# zx81_kbd.net
KiCad netlist of a schematic drawn in EAGLE
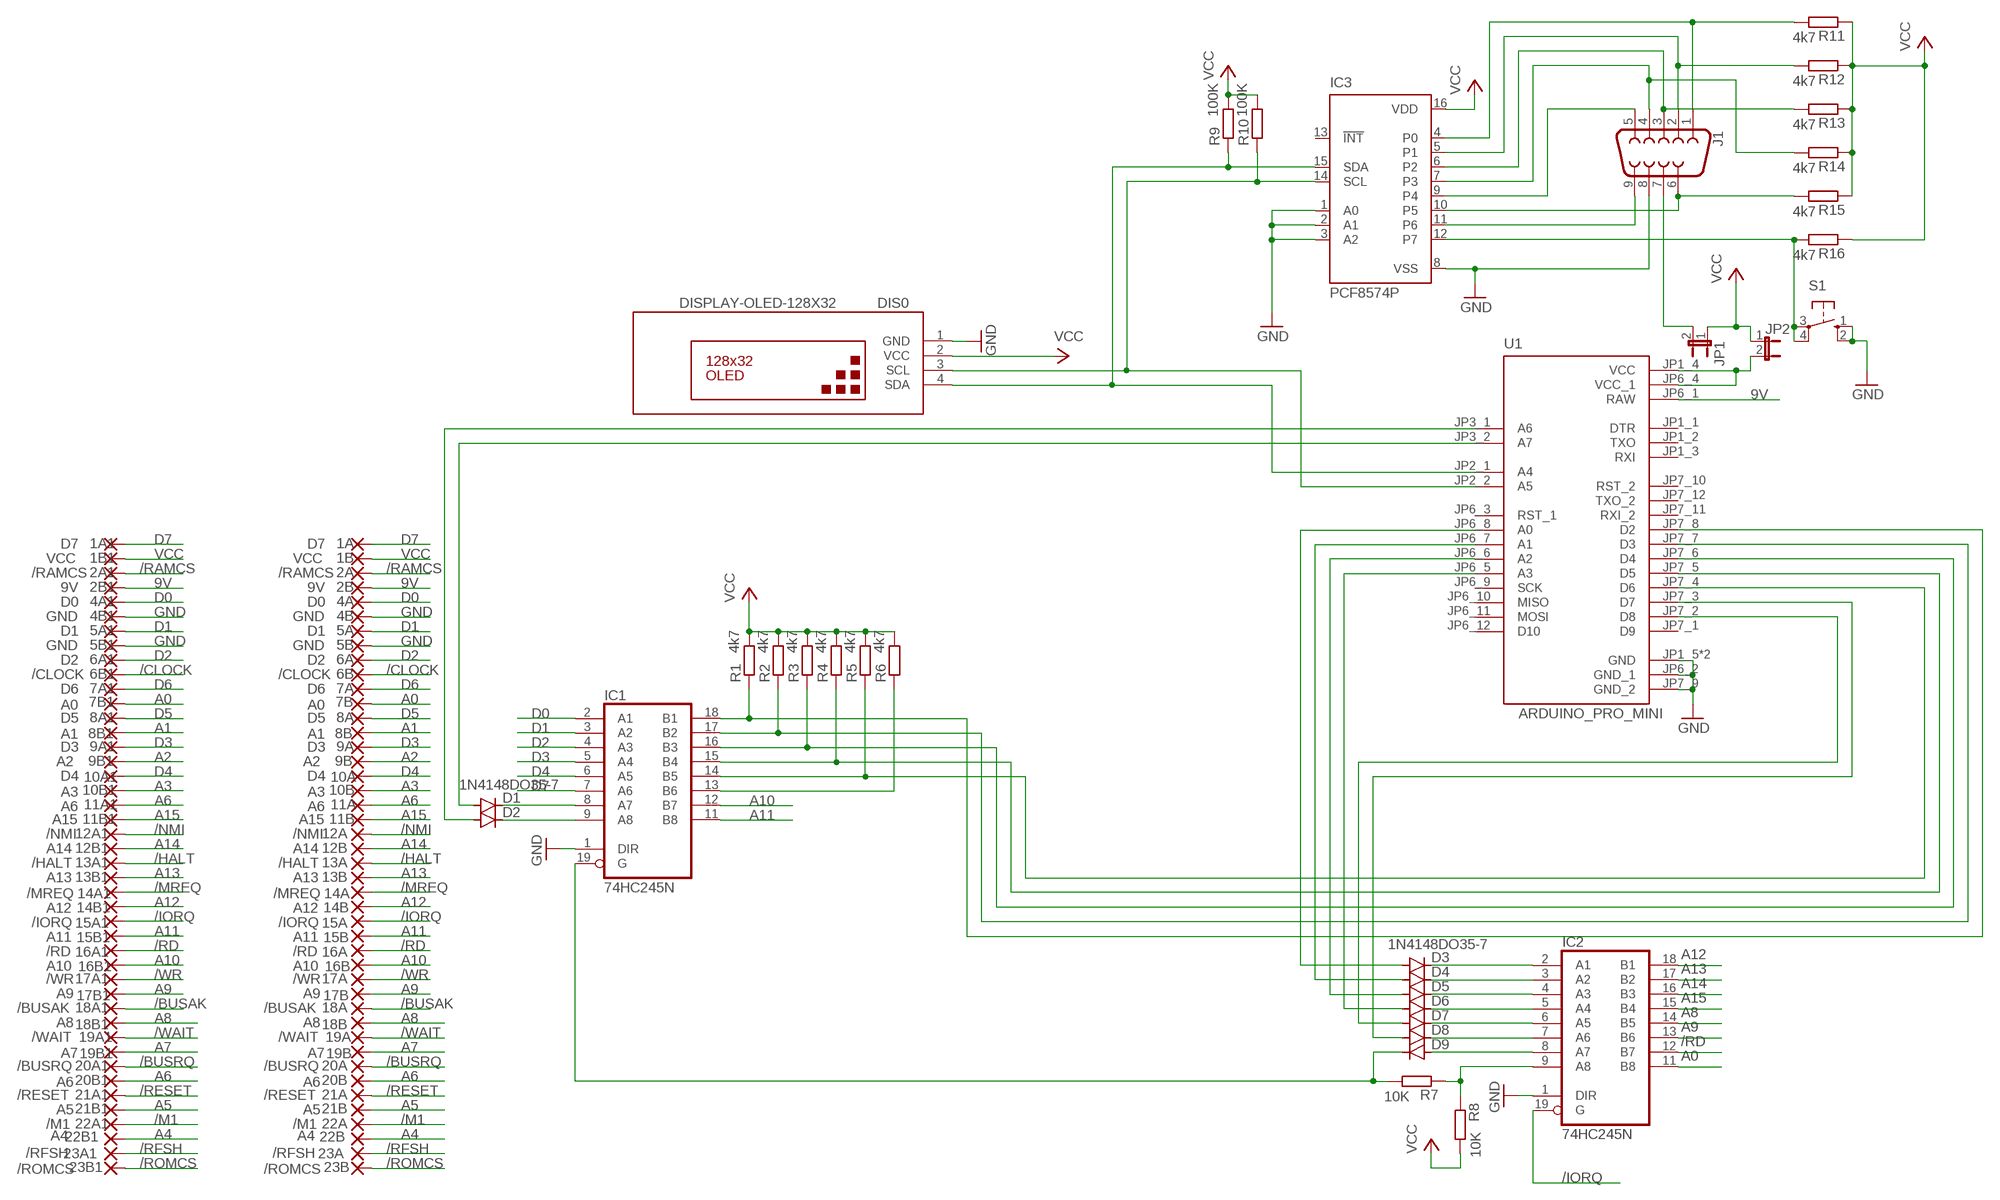
[diagram p0: schematic, sheet 1]

(export (version "E")
  (design (tool "Eeschema 10.0.6"))
  (components
    (comp (ref "1A")
      (value "D7")
      (footprint "eagle-import:EDGEPIN")
      (libsource (lib "eagle-import") (part "SMD2EDGEPIN"))
    )
    (comp (ref "1A1")
      (value "D7")
      (footprint "eagle-import:EDGEPIN")
      (libsource (lib "eagle-import") (part "SMD2EDGEPIN"))
    )
    (comp (ref "1B")
      (value "VCC")
      (footprint "eagle-import:EDGEPIN")
      (libsource (lib "eagle-import") (part "SMD2EDGEPIN"))
    )
    (comp (ref "1B1")
      (value "VCC")
      (footprint "eagle-import:EDGEPIN")
      (libsource (lib "eagle-import") (part "SMD2EDGEPIN"))
    )
    (comp (ref "2A")
      (value "/RAMCS")
      (footprint "eagle-import:EDGEPIN")
      (libsource (lib "eagle-import") (part "SMD2EDGEPIN"))
    )
    (comp (ref "2A1")
      (value "/RAMCS")
      (footprint "eagle-import:EDGEPIN")
      (libsource (lib "eagle-import") (part "SMD2EDGEPIN"))
    )
    (comp (ref "2B")
      (value "9V")
      (footprint "eagle-import:EDGEPIN")
      (libsource (lib "eagle-import") (part "SMD2EDGEPIN"))
    )
    (comp (ref "2B1")
      (value "9V")
      (footprint "eagle-import:EDGEPIN")
      (libsource (lib "eagle-import") (part "SMD2EDGEPIN"))
    )
    (comp (ref "4A")
      (value "D0")
      (footprint "eagle-import:EDGEPIN")
      (libsource (lib "eagle-import") (part "SMD2EDGEPIN"))
    )
    (comp (ref "4A1")
      (value "D0")
      (footprint "eagle-import:EDGEPIN")
      (libsource (lib "eagle-import") (part "SMD2EDGEPIN"))
    )
    (comp (ref "4B")
      (value "GND")
      (footprint "eagle-import:EDGEPIN")
      (libsource (lib "eagle-import") (part "SMD2EDGEPIN"))
    )
    (comp (ref "4B1")
      (value "GND")
      (footprint "eagle-import:EDGEPIN")
      (libsource (lib "eagle-import") (part "SMD2EDGEPIN"))
    )
    (comp (ref "5A")
      (value "D1")
      (footprint "eagle-import:EDGEPIN")
      (libsource (lib "eagle-import") (part "SMD2EDGEPIN"))
    )
    (comp (ref "5A1")
      (value "D1")
      (footprint "eagle-import:EDGEPIN")
      (libsource (lib "eagle-import") (part "SMD2EDGEPIN"))
    )
    (comp (ref "5B")
      (value "GND")
      (footprint "eagle-import:EDGEPIN")
      (libsource (lib "eagle-import") (part "SMD2EDGEPIN"))
    )
    (comp (ref "5B1")
      (value "GND")
      (footprint "eagle-import:EDGEPIN")
      (libsource (lib "eagle-import") (part "SMD2EDGEPIN"))
    )
    (comp (ref "6A")
      (value "D2")
      (footprint "eagle-import:EDGEPIN")
      (libsource (lib "eagle-import") (part "SMD2EDGEPIN"))
    )
    (comp (ref "6A1")
      (value "D2")
      (footprint "eagle-import:EDGEPIN")
      (libsource (lib "eagle-import") (part "SMD2EDGEPIN"))
    )
    (comp (ref "6B")
      (value "/CLOCK")
      (footprint "eagle-import:EDGEPIN")
      (libsource (lib "eagle-import") (part "SMD2EDGEPIN"))
    )
    (comp (ref "6B1")
      (value "/CLOCK")
      (footprint "eagle-import:EDGEPIN")
      (libsource (lib "eagle-import") (part "SMD2EDGEPIN"))
    )
    (comp (ref "7A")
      (value "D6")
      (footprint "eagle-import:EDGEPIN")
      (libsource (lib "eagle-import") (part "SMD2EDGEPIN"))
    )
    (comp (ref "7A1")
      (value "D6")
      (footprint "eagle-import:EDGEPIN")
      (libsource (lib "eagle-import") (part "SMD2EDGEPIN"))
    )
    (comp (ref "7B")
      (value "A0")
      (footprint "eagle-import:EDGEPIN")
      (libsource (lib "eagle-import") (part "SMD2EDGEPIN"))
    )
    (comp (ref "7B1")
      (value "A0")
      (footprint "eagle-import:EDGEPIN")
      (libsource (lib "eagle-import") (part "SMD2EDGEPIN"))
    )
    (comp (ref "8A")
      (value "D5")
      (footprint "eagle-import:EDGEPIN")
      (libsource (lib "eagle-import") (part "SMD2EDGEPIN"))
    )
    (comp (ref "8A1")
      (value "D5")
      (footprint "eagle-import:EDGEPIN")
      (libsource (lib "eagle-import") (part "SMD2EDGEPIN"))
    )
    (comp (ref "8B")
      (value "A1")
      (footprint "eagle-import:EDGEPIN")
      (libsource (lib "eagle-import") (part "SMD2EDGEPIN"))
    )
    (comp (ref "8B1")
      (value "A1")
      (footprint "eagle-import:EDGEPIN")
      (libsource (lib "eagle-import") (part "SMD2EDGEPIN"))
    )
    (comp (ref "9A")
      (value "D3")
      (footprint "eagle-import:EDGEPIN")
      (libsource (lib "eagle-import") (part "SMD2EDGEPIN"))
    )
    (comp (ref "9A1")
      (value "D3")
      (footprint "eagle-import:EDGEPIN")
      (libsource (lib "eagle-import") (part "SMD2EDGEPIN"))
    )
    (comp (ref "9B")
      (value "A2")
      (footprint "eagle-import:EDGEPIN")
      (libsource (lib "eagle-import") (part "SMD2EDGEPIN"))
    )
    (comp (ref "9B1")
      (value "A2")
      (footprint "eagle-import:EDGEPIN")
      (libsource (lib "eagle-import") (part "SMD2EDGEPIN"))
    )
    (comp (ref "10A")
      (value "D4")
      (footprint "eagle-import:EDGEPIN")
      (libsource (lib "eagle-import") (part "SMD2EDGEPIN"))
    )
    (comp (ref "10A1")
      (value "D4")
      (footprint "eagle-import:EDGEPIN")
      (libsource (lib "eagle-import") (part "SMD2EDGEPIN"))
    )
    (comp (ref "10B")
      (value "A3")
      (footprint "eagle-import:EDGEPIN")
      (libsource (lib "eagle-import") (part "SMD2EDGEPIN"))
    )
    (comp (ref "10B1")
      (value "A3")
      (footprint "eagle-import:EDGEPIN")
      (libsource (lib "eagle-import") (part "SMD2EDGEPIN"))
    )
    (comp (ref "11A")
      (value "A6")
      (footprint "eagle-import:EDGEPIN")
      (libsource (lib "eagle-import") (part "SMD2EDGEPIN"))
    )
    (comp (ref "11A1")
      (value "A6")
      (footprint "eagle-import:EDGEPIN")
      (libsource (lib "eagle-import") (part "SMD2EDGEPIN"))
    )
    (comp (ref "11B")
      (value "A15")
      (footprint "eagle-import:EDGEPIN")
      (libsource (lib "eagle-import") (part "SMD2EDGEPIN"))
    )
    (comp (ref "11B1")
      (value "A15")
      (footprint "eagle-import:EDGEPIN")
      (libsource (lib "eagle-import") (part "SMD2EDGEPIN"))
    )
    (comp (ref "12A")
      (value "/NMI")
      (footprint "eagle-import:EDGEPIN")
      (libsource (lib "eagle-import") (part "SMD2EDGEPIN"))
    )
    (comp (ref "12A1")
      (value "/NMI")
      (footprint "eagle-import:EDGEPIN")
      (libsource (lib "eagle-import") (part "SMD2EDGEPIN"))
    )
    (comp (ref "12B")
      (value "A14")
      (footprint "eagle-import:EDGEPIN")
      (libsource (lib "eagle-import") (part "SMD2EDGEPIN"))
    )
    (comp (ref "12B1")
      (value "A14")
      (footprint "eagle-import:EDGEPIN")
      (libsource (lib "eagle-import") (part "SMD2EDGEPIN"))
    )
    (comp (ref "13A")
      (value "/HALT")
      (footprint "eagle-import:EDGEPIN")
      (libsource (lib "eagle-import") (part "SMD2EDGEPIN"))
    )
    (comp (ref "13A1")
      (value "/HALT")
      (footprint "eagle-import:EDGEPIN")
      (libsource (lib "eagle-import") (part "SMD2EDGEPIN"))
    )
    (comp (ref "13B")
      (value "A13")
      (footprint "eagle-import:EDGEPIN")
      (libsource (lib "eagle-import") (part "SMD2EDGEPIN"))
    )
    (comp (ref "13B1")
      (value "A13")
      (footprint "eagle-import:EDGEPIN")
      (libsource (lib "eagle-import") (part "SMD2EDGEPIN"))
    )
    (comp (ref "14A")
      (value "/MREQ")
      (footprint "eagle-import:EDGEPIN")
      (libsource (lib "eagle-import") (part "SMD2EDGEPIN"))
    )
    (comp (ref "14A1")
      (value "/MREQ")
      (footprint "eagle-import:EDGEPIN")
      (libsource (lib "eagle-import") (part "SMD2EDGEPIN"))
    )
    (comp (ref "14B")
      (value "A12")
      (footprint "eagle-import:EDGEPIN")
      (libsource (lib "eagle-import") (part "SMD2EDGEPIN"))
    )
    (comp (ref "14B1")
      (value "A12")
      (footprint "eagle-import:EDGEPIN")
      (libsource (lib "eagle-import") (part "SMD2EDGEPIN"))
    )
    (comp (ref "15A")
      (value "/IORQ")
      (footprint "eagle-import:EDGEPIN")
      (libsource (lib "eagle-import") (part "SMD2EDGEPIN"))
    )
    (comp (ref "15A1")
      (value "/IORQ")
      (footprint "eagle-import:EDGEPIN")
      (libsource (lib "eagle-import") (part "SMD2EDGEPIN"))
    )
    (comp (ref "15B")
      (value "A11")
      (footprint "eagle-import:EDGEPIN")
      (libsource (lib "eagle-import") (part "SMD2EDGEPIN"))
    )
    (comp (ref "15B1")
      (value "A11")
      (footprint "eagle-import:EDGEPIN")
      (libsource (lib "eagle-import") (part "SMD2EDGEPIN"))
    )
    (comp (ref "16A")
      (value "/RD")
      (footprint "eagle-import:EDGEPIN")
      (libsource (lib "eagle-import") (part "SMD2EDGEPIN"))
    )
    (comp (ref "16A1")
      (value "/RD")
      (footprint "eagle-import:EDGEPIN")
      (libsource (lib "eagle-import") (part "SMD2EDGEPIN"))
    )
    (comp (ref "16B")
      (value "A10")
      (footprint "eagle-import:EDGEPIN")
      (libsource (lib "eagle-import") (part "SMD2EDGEPIN"))
    )
    (comp (ref "16B1")
      (value "A10")
      (footprint "eagle-import:EDGEPIN")
      (libsource (lib "eagle-import") (part "SMD2EDGEPIN"))
    )
    (comp (ref "17A")
      (value "/WR")
      (footprint "eagle-import:EDGEPIN")
      (libsource (lib "eagle-import") (part "SMD2EDGEPIN"))
    )
    (comp (ref "17A1")
      (value "/WR")
      (footprint "eagle-import:EDGEPIN")
      (libsource (lib "eagle-import") (part "SMD2EDGEPIN"))
    )
    (comp (ref "17B")
      (value "A9")
      (footprint "eagle-import:EDGEPIN")
      (libsource (lib "eagle-import") (part "SMD2EDGEPIN"))
    )
    (comp (ref "17B1")
      (value "A9")
      (footprint "eagle-import:EDGEPIN")
      (libsource (lib "eagle-import") (part "SMD2EDGEPIN"))
    )
    (comp (ref "18A")
      (value "/BUSAK")
      (footprint "eagle-import:EDGEPIN")
      (libsource (lib "eagle-import") (part "SMD2EDGEPIN"))
    )
    (comp (ref "18A1")
      (value "/BUSAK")
      (footprint "eagle-import:EDGEPIN")
      (libsource (lib "eagle-import") (part "SMD2EDGEPIN"))
    )
    (comp (ref "18B")
      (value "A8")
      (footprint "eagle-import:EDGEPIN")
      (libsource (lib "eagle-import") (part "SMD2EDGEPIN"))
    )
    (comp (ref "18B1")
      (value "A8")
      (footprint "eagle-import:EDGEPIN")
      (libsource (lib "eagle-import") (part "SMD2EDGEPIN"))
    )
    (comp (ref "19A")
      (value "/WAIT")
      (footprint "eagle-import:EDGEPIN")
      (libsource (lib "eagle-import") (part "SMD2EDGEPIN"))
    )
    (comp (ref "19A1")
      (value "/WAIT")
      (footprint "eagle-import:EDGEPIN")
      (libsource (lib "eagle-import") (part "SMD2EDGEPIN"))
    )
    (comp (ref "19B")
      (value "A7")
      (footprint "eagle-import:EDGEPIN")
      (libsource (lib "eagle-import") (part "SMD2EDGEPIN"))
    )
    (comp (ref "19B1")
      (value "A7")
      (footprint "eagle-import:EDGEPIN")
      (libsource (lib "eagle-import") (part "SMD2EDGEPIN"))
    )
    (comp (ref "20A")
      (value "/BUSRQ")
      (footprint "eagle-import:EDGEPIN")
      (libsource (lib "eagle-import") (part "SMD2EDGEPIN"))
    )
    (comp (ref "20A1")
      (value "/BUSRQ")
      (footprint "eagle-import:EDGEPIN")
      (libsource (lib "eagle-import") (part "SMD2EDGEPIN"))
    )
    (comp (ref "20B")
      (value "A6")
      (footprint "eagle-import:EDGEPIN")
      (libsource (lib "eagle-import") (part "SMD2EDGEPIN"))
    )
    (comp (ref "20B1")
      (value "A6")
      (footprint "eagle-import:EDGEPIN")
      (libsource (lib "eagle-import") (part "SMD2EDGEPIN"))
    )
    (comp (ref "21A")
      (value "/RESET")
      (footprint "eagle-import:EDGEPIN")
      (libsource (lib "eagle-import") (part "SMD2EDGEPIN"))
    )
    (comp (ref "21A1")
      (value "/RESET")
      (footprint "eagle-import:EDGEPIN")
      (libsource (lib "eagle-import") (part "SMD2EDGEPIN"))
    )
    (comp (ref "21B")
      (value "A5")
      (footprint "eagle-import:EDGEPIN")
      (libsource (lib "eagle-import") (part "SMD2EDGEPIN"))
    )
    (comp (ref "21B1")
      (value "A5")
      (footprint "eagle-import:EDGEPIN")
      (libsource (lib "eagle-import") (part "SMD2EDGEPIN"))
    )
    (comp (ref "22A")
      (value "/M1")
      (footprint "eagle-import:EDGEPIN")
      (libsource (lib "eagle-import") (part "SMD2EDGEPIN"))
    )
    (comp (ref "22A1")
      (value "/M1")
      (footprint "eagle-import:EDGEPIN")
      (libsource (lib "eagle-import") (part "SMD2EDGEPIN"))
    )
    (comp (ref "22B")
      (value "A4")
      (footprint "eagle-import:EDGEPIN")
      (libsource (lib "eagle-import") (part "SMD2EDGEPIN"))
    )
    (comp (ref "22B1")
      (value "A4")
      (footprint "eagle-import:EDGEPIN")
      (libsource (lib "eagle-import") (part "SMD2EDGEPIN"))
    )
    (comp (ref "23A")
      (value "/RFSH")
      (footprint "eagle-import:EDGEPIN")
      (libsource (lib "eagle-import") (part "SMD2EDGEPIN"))
    )
    (comp (ref "23A1")
      (value "/RFSH")
      (footprint "eagle-import:EDGEPIN")
      (libsource (lib "eagle-import") (part "SMD2EDGEPIN"))
    )
    (comp (ref "23B")
      (value "/ROMCS")
      (footprint "eagle-import:EDGEPIN")
      (libsource (lib "eagle-import") (part "SMD2EDGEPIN"))
    )
    (comp (ref "23B1")
      (value "/ROMCS")
      (footprint "eagle-import:EDGEPIN")
      (libsource (lib "eagle-import") (part "SMD2EDGEPIN"))
    )
    (comp (ref "D1")
      (value "1N4148DO35-7")
      (footprint "eagle-import:DO35-7")
      (libsource (lib "eagle-import") (part "1N4148DO35-7"))
    )
    (comp (ref "D2")
      (value "1N4148DO35-7")
      (footprint "eagle-import:DO35-7")
      (libsource (lib "eagle-import") (part "1N4148DO35-7"))
    )
    (comp (ref "D3")
      (value "1N4148DO35-7")
      (footprint "eagle-import:DO35-7")
      (libsource (lib "eagle-import") (part "1N4148DO35-7"))
    )
    (comp (ref "D4")
      (value "1N4148DO35-7")
      (footprint "eagle-import:DO35-7")
      (libsource (lib "eagle-import") (part "1N4148DO35-7"))
    )
    (comp (ref "D5")
      (value "1N4148DO35-7")
      (footprint "eagle-import:DO35-7")
      (libsource (lib "eagle-import") (part "1N4148DO35-7"))
    )
    (comp (ref "D6")
      (value "1N4148DO35-7")
      (footprint "eagle-import:DO35-7")
      (libsource (lib "eagle-import") (part "1N4148DO35-7"))
    )
    (comp (ref "D7")
      (value "1N4148DO35-7")
      (footprint "eagle-import:DO35-7")
      (libsource (lib "eagle-import") (part "1N4148DO35-7"))
    )
    (comp (ref "D8")
      (value "1N4148DO35-7")
      (footprint "eagle-import:DO35-7")
      (libsource (lib "eagle-import") (part "1N4148DO35-7"))
    )
    (comp (ref "D9")
      (value "1N4148DO35-7")
      (footprint "eagle-import:DO35-7")
      (libsource (lib "eagle-import") (part "1N4148DO35-7"))
    )
    (comp (ref "DIS0")
      (value "DISPLAY-OLED-128X32")
      (footprint "eagle-import:DISPLAY-OLED-128X32")
      (libsource (lib "eagle-import") (part "DISPLAY-OLED-128X32"))
    )
    (comp (ref "IC1")
      (value "74HC245N")
      (footprint "eagle-import:DIL20")
      (libsource (lib "eagle-import") (part "74245NHC"))
    )
    (comp (ref "IC2")
      (value "74HC245N")
      (footprint "eagle-import:DIL20")
      (libsource (lib "eagle-import") (part "74245NHC"))
    )
    (comp (ref "IC3")
      (value "PCF8574P")
      (footprint "eagle-import:DIL16")
      (fields (field (name "MPN") "PCF8574PN"))
      (libsource (lib "eagle-import") (part "PCF8574P"))
    )
    (comp (ref "J1")
      (value "DB9MALE")
      (footprint "eagle-import:DB9_MALE")
      (libsource (lib "eagle-import") (part "DB9MALE"))
    )
    (comp (ref "JP1")
      (value "JP1E")
      (footprint "eagle-import:JP1")
      (libsource (lib "eagle-import") (part "JP1E"))
    )
    (comp (ref "JP2")
      (value "JP1E")
      (footprint "eagle-import:JP1")
      (libsource (lib "eagle-import") (part "JP1E"))
    )
    (comp (ref "R1")
      (value "4k7")
      (footprint "eagle-import:0204_7")
      (libsource (lib "eagle-import") (part "R-EU_0204/7"))
    )
    (comp (ref "R2")
      (value "4k7")
      (footprint "eagle-import:0204_7")
      (libsource (lib "eagle-import") (part "R-EU_0204/7"))
    )
    (comp (ref "R3")
      (value "4k7")
      (footprint "eagle-import:0204_7")
      (libsource (lib "eagle-import") (part "R-EU_0204/7"))
    )
    (comp (ref "R4")
      (value "4k7")
      (footprint "eagle-import:0204_7")
      (libsource (lib "eagle-import") (part "R-EU_0204/7"))
    )
    (comp (ref "R5")
      (value "4k7")
      (footprint "eagle-import:0204_7")
      (libsource (lib "eagle-import") (part "R-EU_0204/7"))
    )
    (comp (ref "R6")
      (value "4k7")
      (footprint "eagle-import:0204_7")
      (libsource (lib "eagle-import") (part "R-EU_0204/7"))
    )
    (comp (ref "R7")
      (value "10K")
      (footprint "eagle-import:0204_7")
      (libsource (lib "eagle-import") (part "R-EU_0204/7"))
    )
    (comp (ref "R8")
      (value "10K")
      (footprint "eagle-import:0204_7")
      (libsource (lib "eagle-import") (part "R-EU_0204/7"))
    )
    (comp (ref "R9")
      (value "100K")
      (footprint "eagle-import:0204_7")
      (libsource (lib "eagle-import") (part "R-EU_0204/7"))
    )
    (comp (ref "R10")
      (value "100K")
      (footprint "eagle-import:0204_7")
      (libsource (lib "eagle-import") (part "R-EU_0204/7"))
    )
    (comp (ref "R11")
      (value "4k7")
      (footprint "eagle-import:0204_7")
      (libsource (lib "eagle-import") (part "R-EU_0204/7"))
    )
    (comp (ref "R12")
      (value "4k7")
      (footprint "eagle-import:0204_7")
      (libsource (lib "eagle-import") (part "R-EU_0204/7"))
    )
    (comp (ref "R13")
      (value "4k7")
      (footprint "eagle-import:0204_7")
      (libsource (lib "eagle-import") (part "R-EU_0204/7"))
    )
    (comp (ref "R14")
      (value "4k7")
      (footprint "eagle-import:0204_7")
      (libsource (lib "eagle-import") (part "R-EU_0204/7"))
    )
    (comp (ref "R15")
      (value "4k7")
      (footprint "eagle-import:0204_7")
      (libsource (lib "eagle-import") (part "R-EU_0204/7"))
    )
    (comp (ref "R16")
      (value "4k7")
      (footprint "eagle-import:0204_7")
      (libsource (lib "eagle-import") (part "R-EU_0204/7"))
    )
    (comp (ref "S1")
      (value "10-XX11MM")
      (footprint "eagle-import:B3F-10XX_11MM")
      (libsource (lib "eagle-import") (part "10-XX11MM"))
    )
    (comp (ref "U1")
      (value "ARDUINO_PRO_MINI")
      (footprint "eagle-import:MODULE_ARDUINO_PRO_MINI")
      (fields (field (name "MF") "Arduino") (field (name "MP") "Arduino Pro Mini"))
      (libsource (lib "eagle-import") (part "ARDUINO_PRO_MINI"))
    )
  )
  (nets
    (net (code "1") (name "/9V") (class "Default")
      (node (ref "2B") (pin "1") (pinfunction "P_1") (pintype "passive"))
      (node (ref "2B1") (pin "1") (pinfunction "P_1") (pintype "passive"))
      (node (ref "U1") (pin "JP6_1") (pinfunction "RAW_JP6_1") (pintype "power_in"))
    )
    (net (code "2") (name "/A0") (class "Default")
      (node (ref "7B") (pin "1") (pinfunction "P_1") (pintype "passive"))
      (node (ref "7B1") (pin "1") (pinfunction "P_1") (pintype "passive"))
      (node (ref "IC2") (pin "11") (pinfunction "B8_11") (pintype "bidirectional"))
    )
    (net (code "3") (name "/A1") (class "Default")
      (node (ref "8B") (pin "1") (pinfunction "P_1") (pintype "passive"))
      (node (ref "8B1") (pin "1") (pinfunction "P_1") (pintype "passive"))
    )
    (net (code "4") (name "/A2") (class "Default")
      (node (ref "9B") (pin "1") (pinfunction "P_1") (pintype "passive"))
      (node (ref "9B1") (pin "1") (pinfunction "P_1") (pintype "passive"))
    )
    (net (code "5") (name "/A3") (class "Default")
      (node (ref "10B") (pin "1") (pinfunction "P_1") (pintype "passive"))
      (node (ref "10B1") (pin "1") (pinfunction "P_1") (pintype "passive"))
    )
    (net (code "6") (name "/A4") (class "Default")
      (node (ref "22B") (pin "1") (pinfunction "P_1") (pintype "passive"))
      (node (ref "22B1") (pin "1") (pinfunction "P_1") (pintype "passive"))
    )
    (net (code "7") (name "/A5") (class "Default")
      (node (ref "21B") (pin "1") (pinfunction "P_1") (pintype "passive"))
      (node (ref "21B1") (pin "1") (pinfunction "P_1") (pintype "passive"))
    )
    (net (code "8") (name "/A6") (class "Default")
      (node (ref "11A") (pin "1") (pinfunction "P_1") (pintype "passive"))
      (node (ref "11A1") (pin "1") (pinfunction "P_1") (pintype "passive"))
      (node (ref "20B") (pin "1") (pinfunction "P_1") (pintype "passive"))
      (node (ref "20B1") (pin "1") (pinfunction "P_1") (pintype "passive"))
    )
    (net (code "9") (name "/A7") (class "Default")
      (node (ref "19B") (pin "1") (pinfunction "P_1") (pintype "passive"))
      (node (ref "19B1") (pin "1") (pinfunction "P_1") (pintype "passive"))
    )
    (net (code "10") (name "/A8") (class "Default")
      (node (ref "18B") (pin "1") (pinfunction "P_1") (pintype "passive"))
      (node (ref "18B1") (pin "1") (pinfunction "P_1") (pintype "passive"))
      (node (ref "IC2") (pin "14") (pinfunction "B5_14") (pintype "bidirectional"))
    )
    (net (code "11") (name "/A9") (class "Default")
      (node (ref "17B") (pin "1") (pinfunction "P_1") (pintype "passive"))
      (node (ref "17B1") (pin "1") (pinfunction "P_1") (pintype "passive"))
      (node (ref "IC2") (pin "13") (pinfunction "B6_13") (pintype "bidirectional"))
    )
    (net (code "12") (name "/A10") (class "Default")
      (node (ref "16B") (pin "1") (pinfunction "P_1") (pintype "passive"))
      (node (ref "16B1") (pin "1") (pinfunction "P_1") (pintype "passive"))
      (node (ref "IC1") (pin "12") (pinfunction "B7_12") (pintype "bidirectional"))
    )
    (net (code "13") (name "/A11") (class "Default")
      (node (ref "15B") (pin "1") (pinfunction "P_1") (pintype "passive"))
      (node (ref "15B1") (pin "1") (pinfunction "P_1") (pintype "passive"))
      (node (ref "IC1") (pin "11") (pinfunction "B8_11") (pintype "bidirectional"))
    )
    (net (code "14") (name "/A12") (class "Default")
      (node (ref "14B") (pin "1") (pinfunction "P_1") (pintype "passive"))
      (node (ref "14B1") (pin "1") (pinfunction "P_1") (pintype "passive"))
      (node (ref "IC2") (pin "18") (pinfunction "B1_18") (pintype "bidirectional"))
    )
    (net (code "15") (name "/A13") (class "Default")
      (node (ref "13B") (pin "1") (pinfunction "P_1") (pintype "passive"))
      (node (ref "13B1") (pin "1") (pinfunction "P_1") (pintype "passive"))
      (node (ref "IC2") (pin "17") (pinfunction "B2_17") (pintype "bidirectional"))
    )
    (net (code "16") (name "/A14") (class "Default")
      (node (ref "12B") (pin "1") (pinfunction "P_1") (pintype "passive"))
      (node (ref "12B1") (pin "1") (pinfunction "P_1") (pintype "passive"))
      (node (ref "IC2") (pin "16") (pinfunction "B3_16") (pintype "bidirectional"))
    )
    (net (code "17") (name "/A15") (class "Default")
      (node (ref "11B") (pin "1") (pinfunction "P_1") (pintype "passive"))
      (node (ref "11B1") (pin "1") (pinfunction "P_1") (pintype "passive"))
      (node (ref "IC2") (pin "15") (pinfunction "B4_15") (pintype "bidirectional"))
    )
    (net (code "18") (name "/D0") (class "Default")
      (node (ref "4A") (pin "1") (pinfunction "P_1") (pintype "passive"))
      (node (ref "4A1") (pin "1") (pinfunction "P_1") (pintype "passive"))
      (node (ref "IC1") (pin "2") (pinfunction "A1_2") (pintype "bidirectional"))
    )
    (net (code "19") (name "/D1") (class "Default")
      (node (ref "5A") (pin "1") (pinfunction "P_1") (pintype "passive"))
      (node (ref "5A1") (pin "1") (pinfunction "P_1") (pintype "passive"))
      (node (ref "IC1") (pin "3") (pinfunction "A2_3") (pintype "bidirectional"))
    )
    (net (code "20") (name "/D2") (class "Default")
      (node (ref "6A") (pin "1") (pinfunction "P_1") (pintype "passive"))
      (node (ref "6A1") (pin "1") (pinfunction "P_1") (pintype "passive"))
      (node (ref "IC1") (pin "4") (pinfunction "A3_4") (pintype "bidirectional"))
    )
    (net (code "21") (name "/D3") (class "Default")
      (node (ref "9A") (pin "1") (pinfunction "P_1") (pintype "passive"))
      (node (ref "9A1") (pin "1") (pinfunction "P_1") (pintype "passive"))
      (node (ref "IC1") (pin "5") (pinfunction "A4_5") (pintype "bidirectional"))
    )
    (net (code "22") (name "/D4") (class "Default")
      (node (ref "10A") (pin "1") (pinfunction "P_1") (pintype "passive"))
      (node (ref "10A1") (pin "1") (pinfunction "P_1") (pintype "passive"))
      (node (ref "IC1") (pin "6") (pinfunction "A5_6") (pintype "bidirectional"))
    )
    (net (code "23") (name "/D5") (class "Default")
      (node (ref "8A") (pin "1") (pinfunction "P_1") (pintype "passive"))
      (node (ref "8A1") (pin "1") (pinfunction "P_1") (pintype "passive"))
    )
    (net (code "24") (name "/D6") (class "Default")
      (node (ref "7A") (pin "1") (pinfunction "P_1") (pintype "passive"))
      (node (ref "7A1") (pin "1") (pinfunction "P_1") (pintype "passive"))
    )
    (net (code "25") (name "/D7") (class "Default")
      (node (ref "1A") (pin "1") (pinfunction "P_1") (pintype "passive"))
      (node (ref "1A1") (pin "1") (pinfunction "P_1") (pintype "passive"))
      (node (ref "IC1") (pin "7") (pinfunction "A6_7") (pintype "bidirectional"))
    )
    (net (code "26") (name "/{slash}BUSAK") (class "Default")
      (node (ref "18A") (pin "1") (pinfunction "P_1") (pintype "passive"))
      (node (ref "18A1") (pin "1") (pinfunction "P_1") (pintype "passive"))
    )
    (net (code "27") (name "/{slash}BUSRQ") (class "Default")
      (node (ref "20A") (pin "1") (pinfunction "P_1") (pintype "passive"))
      (node (ref "20A1") (pin "1") (pinfunction "P_1") (pintype "passive"))
    )
    (net (code "28") (name "/{slash}CLOCK") (class "Default")
      (node (ref "6B") (pin "1") (pinfunction "P_1") (pintype "passive"))
      (node (ref "6B1") (pin "1") (pinfunction "P_1") (pintype "passive"))
    )
    (net (code "29") (name "/{slash}HALT") (class "Default")
      (node (ref "13A") (pin "1") (pinfunction "P_1") (pintype "passive"))
      (node (ref "13A1") (pin "1") (pinfunction "P_1") (pintype "passive"))
    )
    (net (code "30") (name "/{slash}IORQ") (class "Default")
      (node (ref "15A") (pin "1") (pinfunction "P_1") (pintype "passive"))
      (node (ref "15A1") (pin "1") (pinfunction "P_1") (pintype "passive"))
      (node (ref "IC2") (pin "19") (pinfunction "G_19") (pintype "input"))
    )
    (net (code "31") (name "/{slash}M1") (class "Default")
      (node (ref "22A") (pin "1") (pinfunction "P_1") (pintype "passive"))
      (node (ref "22A1") (pin "1") (pinfunction "P_1") (pintype "passive"))
    )
    (net (code "32") (name "/{slash}MREQ") (class "Default")
      (node (ref "14A") (pin "1") (pinfunction "P_1") (pintype "passive"))
      (node (ref "14A1") (pin "1") (pinfunction "P_1") (pintype "passive"))
    )
    (net (code "33") (name "/{slash}NMI") (class "Default")
      (node (ref "12A") (pin "1") (pinfunction "P_1") (pintype "passive"))
      (node (ref "12A1") (pin "1") (pinfunction "P_1") (pintype "passive"))
    )
    (net (code "34") (name "/{slash}RAMCS") (class "Default")
      (node (ref "2A") (pin "1") (pinfunction "P_1") (pintype "passive"))
      (node (ref "2A1") (pin "1") (pinfunction "P_1") (pintype "passive"))
    )
    (net (code "35") (name "/{slash}RD") (class "Default")
      (node (ref "16A") (pin "1") (pinfunction "P_1") (pintype "passive"))
      (node (ref "16A1") (pin "1") (pinfunction "P_1") (pintype "passive"))
      (node (ref "IC2") (pin "12") (pinfunction "B7_12") (pintype "bidirectional"))
    )
    (net (code "36") (name "/{slash}RESET") (class "Default")
      (node (ref "21A") (pin "1") (pinfunction "P_1") (pintype "passive"))
      (node (ref "21A1") (pin "1") (pinfunction "P_1") (pintype "passive"))
    )
    (net (code "37") (name "/{slash}RFSH") (class "Default")
      (node (ref "23A") (pin "1") (pinfunction "P_1") (pintype "passive"))
      (node (ref "23A1") (pin "1") (pinfunction "P_1") (pintype "passive"))
    )
    (net (code "38") (name "/{slash}ROMCS") (class "Default")
      (node (ref "23B") (pin "1") (pinfunction "P_1") (pintype "passive"))
      (node (ref "23B1") (pin "1") (pinfunction "P_1") (pintype "passive"))
    )
    (net (code "39") (name "/{slash}WAIT") (class "Default")
      (node (ref "19A") (pin "1") (pinfunction "P_1") (pintype "passive"))
      (node (ref "19A1") (pin "1") (pinfunction "P_1") (pintype "passive"))
    )
    (net (code "40") (name "/{slash}WR") (class "Default")
      (node (ref "17A") (pin "1") (pinfunction "P_1") (pintype "passive"))
      (node (ref "17A1") (pin "1") (pinfunction "P_1") (pintype "passive"))
    )
    (net (code "41") (name "GND") (class "Default")
      (node (ref "4B") (pin "1") (pinfunction "P_1") (pintype "passive"))
      (node (ref "4B1") (pin "1") (pinfunction "P_1") (pintype "passive"))
      (node (ref "5B") (pin "1") (pinfunction "P_1") (pintype "passive"))
      (node (ref "5B1") (pin "1") (pinfunction "P_1") (pintype "passive"))
      (node (ref "DIS0") (pin "1") (pinfunction "GND_1") (pintype "power_in"))
      (node (ref "IC1") (pin "1") (pinfunction "DIR_1") (pintype "input"))
      (node (ref "IC2") (pin "1") (pinfunction "DIR_1") (pintype "input"))
      (node (ref "IC3") (pin "1") (pinfunction "A0_1") (pintype "input"))
      (node (ref "IC3") (pin "2") (pinfunction "A1_2") (pintype "input"))
      (node (ref "IC3") (pin "3") (pinfunction "A2_3") (pintype "input"))
      (node (ref "IC3") (pin "8") (pinfunction "VSS_8") (pintype "power_in"))
      (node (ref "J1") (pin "8") (pinfunction "8_8") (pintype "passive"))
      (node (ref "S1") (pin "1") (pinfunction "S_1") (pintype "passive"))
      (node (ref "S1") (pin "2") (pinfunction "S1_2") (pintype "passive"))
      (node (ref "U1") (pin "JP1_5") (pinfunction "GND_JP1_5") (pintype "power_in"))
      (node (ref "U1") (pin "JP1_6") (pinfunction "GND_JP1_6") (pintype "power_in"))
      (node (ref "U1") (pin "JP6_2") (pinfunction "GND_1_JP6_2") (pintype "power_in"))
      (node (ref "U1") (pin "JP7_9") (pinfunction "GND_2_JP7_9") (pintype "power_in"))
    )
    (net (code "42") (name "Net-(DIS0-SCL)") (class "Default")
      (node (ref "DIS0") (pin "3") (pinfunction "SCL_3") (pintype "bidirectional"))
      (node (ref "IC3") (pin "14") (pinfunction "SCL_14") (pintype "input"))
      (node (ref "R10") (pin "1") (pinfunction "1_1") (pintype "passive"))
      (node (ref "U1") (pin "JP2_2") (pinfunction "A5_JP2_2") (pintype "bidirectional"))
    )
    (net (code "43") (name "Net-(DIS0-SDA)") (class "Default")
      (node (ref "DIS0") (pin "4") (pinfunction "SDA_4") (pintype "bidirectional"))
      (node (ref "IC3") (pin "15") (pinfunction "SDA_15") (pintype "bidirectional"))
      (node (ref "R9") (pin "1") (pinfunction "1_1") (pintype "passive"))
      (node (ref "U1") (pin "JP2_1") (pinfunction "A4_JP2_1") (pintype "bidirectional"))
    )
    (net (code "44") (name "Net-(IC1A-A7)") (class "Default")
      (node (ref "D1") (pin "C") (pinfunction "C_C") (pintype "passive"))
      (node (ref "IC1") (pin "8") (pinfunction "A7_8") (pintype "bidirectional"))
    )
    (net (code "45") (name "Net-(IC1A-A8)") (class "Default")
      (node (ref "D2") (pin "C") (pinfunction "C_C") (pintype "passive"))
      (node (ref "IC1") (pin "9") (pinfunction "A8_9") (pintype "bidirectional"))
    )
    (net (code "46") (name "Net-(IC1A-B1)") (class "Default")
      (node (ref "IC1") (pin "18") (pinfunction "B1_18") (pintype "bidirectional"))
      (node (ref "R1") (pin "1") (pinfunction "1_1") (pintype "passive"))
      (node (ref "U1") (pin "JP7_8") (pinfunction "D2_JP7_8") (pintype "bidirectional"))
    )
    (net (code "47") (name "Net-(IC1A-B2)") (class "Default")
      (node (ref "IC1") (pin "17") (pinfunction "B2_17") (pintype "bidirectional"))
      (node (ref "R2") (pin "1") (pinfunction "1_1") (pintype "passive"))
      (node (ref "U1") (pin "JP7_7") (pinfunction "D3_JP7_7") (pintype "bidirectional"))
    )
    (net (code "48") (name "Net-(IC1A-B3)") (class "Default")
      (node (ref "IC1") (pin "16") (pinfunction "B3_16") (pintype "bidirectional"))
      (node (ref "R3") (pin "1") (pinfunction "1_1") (pintype "passive"))
      (node (ref "U1") (pin "JP7_6") (pinfunction "D4_JP7_6") (pintype "bidirectional"))
    )
    (net (code "49") (name "Net-(IC1A-B4)") (class "Default")
      (node (ref "IC1") (pin "15") (pinfunction "B4_15") (pintype "bidirectional"))
      (node (ref "R4") (pin "1") (pinfunction "1_1") (pintype "passive"))
      (node (ref "U1") (pin "JP7_5") (pinfunction "D5_JP7_5") (pintype "bidirectional"))
    )
    (net (code "50") (name "Net-(IC1A-B5)") (class "Default")
      (node (ref "IC1") (pin "14") (pinfunction "B5_14") (pintype "bidirectional"))
      (node (ref "R5") (pin "1") (pinfunction "1_1") (pintype "passive"))
      (node (ref "U1") (pin "JP7_4") (pinfunction "D6_JP7_4") (pintype "bidirectional"))
    )
    (net (code "51") (name "Net-(IC1A-B6)") (class "Default")
      (node (ref "IC1") (pin "13") (pinfunction "B6_13") (pintype "bidirectional"))
      (node (ref "R6") (pin "1") (pinfunction "1_1") (pintype "passive"))
    )
    (net (code "52") (name "Net-(IC1A-G)") (class "Default")
      (node (ref "D9") (pin "C") (pinfunction "C_C") (pintype "passive"))
      (node (ref "IC1") (pin "19") (pinfunction "G_19") (pintype "input"))
      (node (ref "R7") (pin "2") (pinfunction "2_2") (pintype "passive"))
    )
    (net (code "53") (name "Net-(IC2A-A1)") (class "Default")
      (node (ref "D3") (pin "C") (pinfunction "C_C") (pintype "passive"))
      (node (ref "IC2") (pin "2") (pinfunction "A1_2") (pintype "bidirectional"))
    )
    (net (code "54") (name "Net-(IC2A-A2)") (class "Default")
      (node (ref "D4") (pin "C") (pinfunction "C_C") (pintype "passive"))
      (node (ref "IC2") (pin "3") (pinfunction "A2_3") (pintype "bidirectional"))
    )
    (net (code "55") (name "Net-(IC2A-A3)") (class "Default")
      (node (ref "D5") (pin "C") (pinfunction "C_C") (pintype "passive"))
      (node (ref "IC2") (pin "4") (pinfunction "A3_4") (pintype "bidirectional"))
    )
    (net (code "56") (name "Net-(IC2A-A4)") (class "Default")
      (node (ref "D6") (pin "C") (pinfunction "C_C") (pintype "passive"))
      (node (ref "IC2") (pin "5") (pinfunction "A4_5") (pintype "bidirectional"))
    )
    (net (code "57") (name "Net-(IC2A-A5)") (class "Default")
      (node (ref "D7") (pin "C") (pinfunction "C_C") (pintype "passive"))
      (node (ref "IC2") (pin "6") (pinfunction "A5_6") (pintype "bidirectional"))
    )
    (net (code "58") (name "Net-(IC2A-A6)") (class "Default")
      (node (ref "D8") (pin "C") (pinfunction "C_C") (pintype "passive"))
      (node (ref "IC2") (pin "7") (pinfunction "A6_7") (pintype "bidirectional"))
    )
    (net (code "59") (name "Net-(IC2A-A7)") (class "Default")
      (node (ref "D9") (pin "A") (pinfunction "A_A") (pintype "passive"))
      (node (ref "IC2") (pin "8") (pinfunction "A7_8") (pintype "bidirectional"))
    )
    (net (code "60") (name "Net-(IC2A-A8)") (class "Default")
      (node (ref "IC2") (pin "9") (pinfunction "A8_9") (pintype "bidirectional"))
      (node (ref "R7") (pin "1") (pinfunction "1_1") (pintype "passive"))
      (node (ref "R8") (pin "1") (pinfunction "1_1") (pintype "passive"))
    )
    (net (code "61") (name "Net-(IC3-P0)") (class "Default")
      (node (ref "IC3") (pin "4") (pinfunction "P0_4") (pintype "bidirectional"))
      (node (ref "J1") (pin "1") (pinfunction "1_1") (pintype "passive"))
      (node (ref "R11") (pin "2") (pinfunction "2_2") (pintype "passive"))
    )
    (net (code "62") (name "Net-(IC3-P1)") (class "Default")
      (node (ref "IC3") (pin "5") (pinfunction "P1_5") (pintype "bidirectional"))
      (node (ref "J1") (pin "2") (pinfunction "2_2") (pintype "passive"))
      (node (ref "R12") (pin "2") (pinfunction "2_2") (pintype "passive"))
    )
    (net (code "63") (name "Net-(IC3-P2)") (class "Default")
      (node (ref "IC3") (pin "6") (pinfunction "P2_6") (pintype "bidirectional"))
      (node (ref "J1") (pin "3") (pinfunction "3_3") (pintype "passive"))
      (node (ref "R13") (pin "2") (pinfunction "2_2") (pintype "passive"))
    )
    (net (code "64") (name "Net-(IC3-P3)") (class "Default")
      (node (ref "IC3") (pin "7") (pinfunction "P3_7") (pintype "bidirectional"))
      (node (ref "J1") (pin "4") (pinfunction "4_4") (pintype "passive"))
      (node (ref "R14") (pin "2") (pinfunction "2_2") (pintype "passive"))
    )
    (net (code "65") (name "Net-(IC3-P4)") (class "Default")
      (node (ref "IC3") (pin "9") (pinfunction "P4_9") (pintype "bidirectional"))
      (node (ref "J1") (pin "5") (pinfunction "5_5") (pintype "passive"))
    )
    (net (code "66") (name "Net-(IC3-P5)") (class "Default")
      (node (ref "IC3") (pin "10") (pinfunction "P5_10") (pintype "bidirectional"))
      (node (ref "J1") (pin "6") (pinfunction "6_6") (pintype "passive"))
      (node (ref "R15") (pin "2") (pinfunction "2_2") (pintype "passive"))
    )
    (net (code "67") (name "Net-(IC3-P6)") (class "Default")
      (node (ref "IC3") (pin "11") (pinfunction "P6_11") (pintype "bidirectional"))
      (node (ref "J1") (pin "9") (pinfunction "9_9") (pintype "passive"))
    )
    (net (code "68") (name "Net-(IC3-P7)") (class "Default")
      (node (ref "IC3") (pin "12") (pinfunction "P7_12") (pintype "bidirectional"))
      (node (ref "R16") (pin "2") (pinfunction "2_2") (pintype "passive"))
      (node (ref "S1") (pin "3") (pinfunction "P_3") (pintype "passive"))
      (node (ref "S1") (pin "4") (pinfunction "P1_4") (pintype "passive"))
    )
    (net (code "69") (name "Net-(J1-Pad7)") (class "Default")
      (node (ref "J1") (pin "7") (pinfunction "7_7") (pintype "passive"))
      (node (ref "JP1") (pin "2") (pinfunction "2_2") (pintype "passive"))
    )
    (net (code "70") (name "Net-(U1-A0)") (class "Default")
      (node (ref "D3") (pin "A") (pinfunction "A_A") (pintype "passive"))
      (node (ref "U1") (pin "JP6_8") (pinfunction "A0_JP6_8") (pintype "bidirectional"))
    )
    (net (code "71") (name "Net-(U1-A1)") (class "Default")
      (node (ref "D4") (pin "A") (pinfunction "A_A") (pintype "passive"))
      (node (ref "U1") (pin "JP6_7") (pinfunction "A1_JP6_7") (pintype "bidirectional"))
    )
    (net (code "72") (name "Net-(U1-A2)") (class "Default")
      (node (ref "D5") (pin "A") (pinfunction "A_A") (pintype "passive"))
      (node (ref "U1") (pin "JP6_6") (pinfunction "A2_JP6_6") (pintype "bidirectional"))
    )
    (net (code "73") (name "Net-(U1-A3)") (class "Default")
      (node (ref "D6") (pin "A") (pinfunction "A_A") (pintype "passive"))
      (node (ref "U1") (pin "JP6_5") (pinfunction "A3_JP6_5") (pintype "bidirectional"))
    )
    (net (code "74") (name "Net-(U1-A6)") (class "Default")
      (node (ref "D2") (pin "A") (pinfunction "A_A") (pintype "passive"))
      (node (ref "U1") (pin "JP3_1") (pinfunction "A6_JP3_1") (pintype "input"))
    )
    (net (code "75") (name "Net-(U1-A7)") (class "Default")
      (node (ref "D1") (pin "A") (pinfunction "A_A") (pintype "passive"))
      (node (ref "U1") (pin "JP3_2") (pinfunction "A7_JP3_2") (pintype "input"))
    )
    (net (code "76") (name "Net-(U1-D7)") (class "Default")
      (node (ref "D8") (pin "A") (pinfunction "A_A") (pintype "passive"))
      (node (ref "U1") (pin "JP7_3") (pinfunction "D7_JP7_3") (pintype "bidirectional"))
    )
    (net (code "77") (name "Net-(U1-D8)") (class "Default")
      (node (ref "D7") (pin "A") (pinfunction "A_A") (pintype "passive"))
      (node (ref "U1") (pin "JP7_2") (pinfunction "D8_JP7_2") (pintype "bidirectional"))
    )
    (net (code "78") (name "Net-(U1-VCC)") (class "Default")
      (node (ref "JP2") (pin "2") (pinfunction "2_2") (pintype "passive"))
      (node (ref "U1") (pin "JP1_4") (pinfunction "VCC_JP1_4") (pintype "power_in"))
      (node (ref "U1") (pin "JP6_4") (pinfunction "VCC_1_JP6_4") (pintype "power_in"))
    )
    (net (code "79") (name "VCC") (class "Default")
      (node (ref "1B") (pin "1") (pinfunction "P_1") (pintype "passive"))
      (node (ref "1B1") (pin "1") (pinfunction "P_1") (pintype "passive"))
      (node (ref "DIS0") (pin "2") (pinfunction "VCC_2") (pintype "power_in"))
      (node (ref "IC3") (pin "16") (pinfunction "VDD_16") (pintype "power_in"))
      (node (ref "JP1") (pin "1") (pinfunction "1_1") (pintype "passive"))
      (node (ref "JP2") (pin "1") (pinfunction "1_1") (pintype "passive"))
      (node (ref "R1") (pin "2") (pinfunction "2_2") (pintype "passive"))
      (node (ref "R10") (pin "2") (pinfunction "2_2") (pintype "passive"))
      (node (ref "R11") (pin "1") (pinfunction "1_1") (pintype "passive"))
      (node (ref "R12") (pin "1") (pinfunction "1_1") (pintype "passive"))
      (node (ref "R13") (pin "1") (pinfunction "1_1") (pintype "passive"))
      (node (ref "R14") (pin "1") (pinfunction "1_1") (pintype "passive"))
      (node (ref "R15") (pin "1") (pinfunction "1_1") (pintype "passive"))
      (node (ref "R16") (pin "1") (pinfunction "1_1") (pintype "passive"))
      (node (ref "R2") (pin "2") (pinfunction "2_2") (pintype "passive"))
      (node (ref "R3") (pin "2") (pinfunction "2_2") (pintype "passive"))
      (node (ref "R4") (pin "2") (pinfunction "2_2") (pintype "passive"))
      (node (ref "R5") (pin "2") (pinfunction "2_2") (pintype "passive"))
      (node (ref "R6") (pin "2") (pinfunction "2_2") (pintype "passive"))
      (node (ref "R8") (pin "2") (pinfunction "2_2") (pintype "passive"))
      (node (ref "R9") (pin "2") (pinfunction "2_2") (pintype "passive"))
    )
    (net (code "80") (name "unconnected-(IC3-~{INT}-Pad13)") (class "Default")
      (node (ref "IC3") (pin "13") (pinfunction "~{INT}_13") (pintype "output"))
    )
    (net (code "81") (name "unconnected-(U1-D9-PadJP7_1)") (class "Default")
      (node (ref "U1") (pin "JP7_1") (pinfunction "D9_JP7_1") (pintype "bidirectional"))
    )
    (net (code "82") (name "unconnected-(U1-D10-PadJP6_12)") (class "Default")
      (node (ref "U1") (pin "JP6_12") (pinfunction "D10_JP6_12") (pintype "bidirectional"))
    )
    (net (code "83") (name "unconnected-(U1-DTR-PadJP1_1)") (class "Default")
      (node (ref "U1") (pin "JP1_1") (pinfunction "DTR_JP1_1") (pintype "input"))
    )
    (net (code "84") (name "unconnected-(U1-MISO-PadJP6_10)") (class "Default")
      (node (ref "U1") (pin "JP6_10") (pinfunction "MISO_JP6_10") (pintype "bidirectional"))
    )
    (net (code "85") (name "unconnected-(U1-MOSI-PadJP6_11)") (class "Default")
      (node (ref "U1") (pin "JP6_11") (pinfunction "MOSI_JP6_11") (pintype "bidirectional"))
    )
    (net (code "86") (name "unconnected-(U1-RST_1-PadJP6_3)") (class "Default")
      (node (ref "U1") (pin "JP6_3") (pinfunction "RST_1_JP6_3") (pintype "input"))
    )
    (net (code "87") (name "unconnected-(U1-RST_2-PadJP7_10)") (class "Default")
      (node (ref "U1") (pin "JP7_10") (pinfunction "RST_2_JP7_10") (pintype "input"))
    )
    (net (code "88") (name "unconnected-(U1-RXI-PadJP1_3)") (class "Default")
      (node (ref "U1") (pin "JP1_3") (pinfunction "RXI_JP1_3") (pintype "bidirectional"))
    )
    (net (code "89") (name "unconnected-(U1-RXI_2-PadJP7_11)") (class "Default")
      (node (ref "U1") (pin "JP7_11") (pinfunction "RXI_2_JP7_11") (pintype "bidirectional"))
    )
    (net (code "90") (name "unconnected-(U1-SCK-PadJP6_9)") (class "Default")
      (node (ref "U1") (pin "JP6_9") (pinfunction "SCK_JP6_9") (pintype "bidirectional"))
    )
    (net (code "91") (name "unconnected-(U1-TXO-PadJP1_2)") (class "Default")
      (node (ref "U1") (pin "JP1_2") (pinfunction "TXO_JP1_2") (pintype "bidirectional"))
    )
    (net (code "92") (name "unconnected-(U1-TXO_2-PadJP7_12)") (class "Default")
      (node (ref "U1") (pin "JP7_12") (pinfunction "TXO_2_JP7_12") (pintype "bidirectional"))
    )
  )
)
